# RP2040Breakout.net
KiCad netlist of a schematic drawn in EAGLE
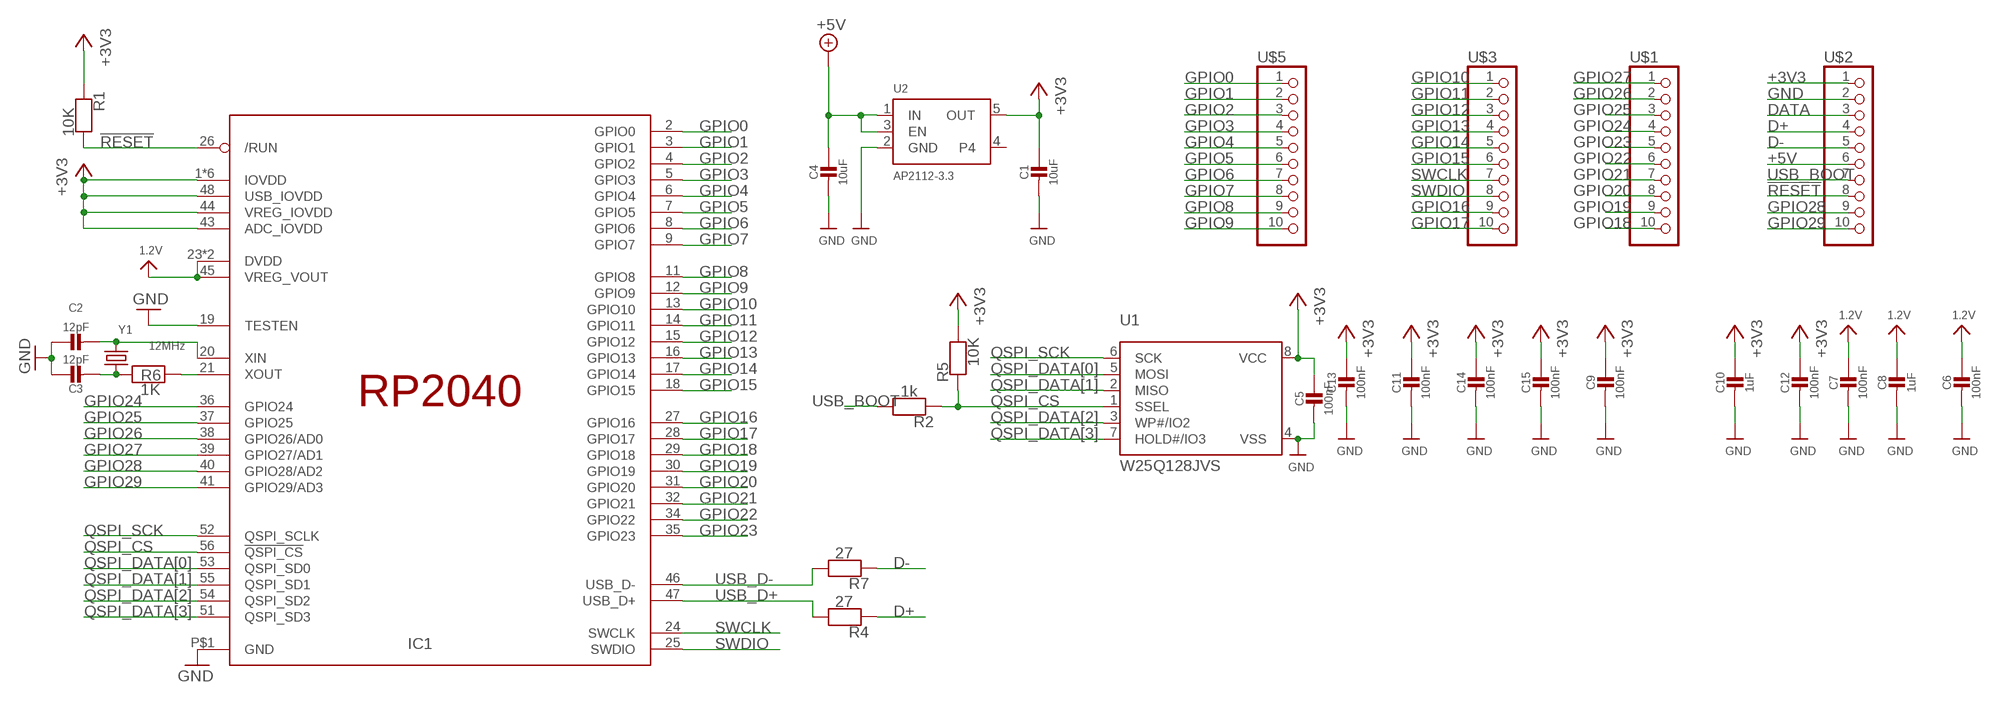
[diagram p0: schematic, sheet 1]

(export (version "E")
  (design (tool "Eeschema 10.0.6"))
  (components
    (comp (ref "C1")
      (value "10uF")
      (footprint "eagle-import:_0805MP")
      (libsource (lib "eagle-import") (part "CAP_CERAMIC_0805MP"))
    )
    (comp (ref "C2")
      (value "12pF")
      (footprint "eagle-import:_0402NO")
      (libsource (lib "eagle-import") (part "CAP_CERAMIC_0402NO"))
    )
    (comp (ref "C3")
      (value "12pF")
      (footprint "eagle-import:_0402NO")
      (libsource (lib "eagle-import") (part "CAP_CERAMIC_0402NO"))
    )
    (comp (ref "C4")
      (value "10uF")
      (footprint "eagle-import:_0805MP")
      (libsource (lib "eagle-import") (part "CAP_CERAMIC_0805MP"))
    )
    (comp (ref "C5")
      (value "100nF")
      (footprint "eagle-import:_0402NO")
      (libsource (lib "eagle-import") (part "CAP_CERAMIC_0402NO"))
    )
    (comp (ref "C6")
      (value "100nF")
      (footprint "eagle-import:_0402NO")
      (libsource (lib "eagle-import") (part "CAP_CERAMIC_0402NO"))
    )
    (comp (ref "C7")
      (value "100nF")
      (footprint "eagle-import:_0402NO")
      (libsource (lib "eagle-import") (part "CAP_CERAMIC_0402NO"))
    )
    (comp (ref "C8")
      (value "1uF")
      (footprint "eagle-import:_0402NO")
      (libsource (lib "eagle-import") (part "CAP_CERAMIC_0402NO"))
    )
    (comp (ref "C9")
      (value "100nF")
      (footprint "eagle-import:_0402NO")
      (libsource (lib "eagle-import") (part "CAP_CERAMIC_0402NO"))
    )
    (comp (ref "C10")
      (value "1uF")
      (footprint "eagle-import:_0402NO")
      (libsource (lib "eagle-import") (part "CAP_CERAMIC_0402NO"))
    )
    (comp (ref "C11")
      (value "100nF")
      (footprint "eagle-import:_0402NO")
      (libsource (lib "eagle-import") (part "CAP_CERAMIC_0402NO"))
    )
    (comp (ref "C12")
      (value "100nF")
      (footprint "eagle-import:_0402NO")
      (libsource (lib "eagle-import") (part "CAP_CERAMIC_0402NO"))
    )
    (comp (ref "C13")
      (value "100nF")
      (footprint "eagle-import:_0402NO")
      (libsource (lib "eagle-import") (part "CAP_CERAMIC_0402NO"))
    )
    (comp (ref "C14")
      (value "100nF")
      (footprint "eagle-import:_0402NO")
      (libsource (lib "eagle-import") (part "CAP_CERAMIC_0402NO"))
    )
    (comp (ref "C15")
      (value "100nF")
      (footprint "eagle-import:_0402NO")
      (libsource (lib "eagle-import") (part "CAP_CERAMIC_0402NO"))
    )
    (comp (ref "IC1")
      (value "RP2040_QFN56")
      (footprint "eagle-import:QFN56_7MM_REDUCEDEPAD")
      (libsource (lib "eagle-import") (part "RP2040_QFN56"))
    )
    (comp (ref "R1")
      (value "10K")
      (footprint "eagle-import:_0402NO")
      (libsource (lib "eagle-import") (part "RESISTOR_0402NO"))
    )
    (comp (ref "R2")
      (value "1k")
      (footprint "eagle-import:_0402NO")
      (libsource (lib "eagle-import") (part "RESISTOR_0402NO"))
    )
    (comp (ref "R4")
      (value "27")
      (footprint "eagle-import:_0402NO")
      (libsource (lib "eagle-import") (part "RESISTOR_0402NO"))
    )
    (comp (ref "R5")
      (value "10K")
      (footprint "eagle-import:_0402NO")
      (libsource (lib "eagle-import") (part "RESISTOR_0402NO"))
    )
    (comp (ref "R6")
      (value "1K")
      (footprint "eagle-import:_0402NO")
      (libsource (lib "eagle-import") (part "RESISTOR_0402NO"))
    )
    (comp (ref "R7")
      (value "27")
      (footprint "eagle-import:_0402NO")
      (libsource (lib "eagle-import") (part "RESISTOR_0402NO"))
    )
    (comp (ref "U$1")
      (value "HEADER-1X10ROUND")
      (footprint "eagle-import:1X10_ROUND")
      (libsource (lib "eagle-import") (part "HEADER-1X10ROUND"))
    )
    (comp (ref "U$2")
      (value "HEADER-1X10ROUND")
      (footprint "eagle-import:1X10_ROUND")
      (libsource (lib "eagle-import") (part "HEADER-1X10ROUND"))
    )
    (comp (ref "U$3")
      (value "HEADER-1X10ROUND")
      (footprint "eagle-import:1X10_ROUND")
      (libsource (lib "eagle-import") (part "HEADER-1X10ROUND"))
    )
    (comp (ref "U$5")
      (value "HEADER-1X10ROUND")
      (footprint "eagle-import:1X10_ROUND")
      (libsource (lib "eagle-import") (part "HEADER-1X10ROUND"))
    )
    (comp (ref "U1")
      (value "W25Q128JVS")
      (footprint "eagle-import:SOIC8_208MIL")
      (libsource (lib "eagle-import") (part "SPIFLASH_8PIN208MIL"))
    )
    (comp (ref "U2")
      (value "AP2112-3.3")
      (footprint "eagle-import:SOT23-5@1")
      (libsource (lib "eagle-import") (part "VREG_SOT23-5"))
    )
    (comp (ref "Y1")
      (value "12MHz")
      (footprint "eagle-import:CRYSTAL-SMD-5X3")
      (libsource (lib "eagle-import") (part "CRYSTALCRYSTAL-SMD-5X3-12MHZ"))
    )
  )
  (nets
    (net (code "1") (name "+3V3") (class "Default")
      (node (ref "C1") (pin "1") (pinfunction "1_1") (pintype "passive"))
      (node (ref "C10") (pin "1") (pinfunction "1_1") (pintype "passive"))
      (node (ref "C11") (pin "1") (pinfunction "1_1") (pintype "passive"))
      (node (ref "C12") (pin "1") (pinfunction "1_1") (pintype "passive"))
      (node (ref "C13") (pin "1") (pinfunction "1_1") (pintype "passive"))
      (node (ref "C14") (pin "1") (pinfunction "1_1") (pintype "passive"))
      (node (ref "C15") (pin "1") (pinfunction "1_1") (pintype "passive"))
      (node (ref "C5") (pin "1") (pinfunction "1_1") (pintype "passive"))
      (node (ref "C9") (pin "1") (pinfunction "1_1") (pintype "passive"))
      (node (ref "IC1") (pin "1") (pinfunction "IOVDD_1") (pintype "power_in"))
      (node (ref "IC1") (pin "10") (pinfunction "IOVDD_10") (pintype "power_in"))
      (node (ref "IC1") (pin "22") (pinfunction "IOVDD_22") (pintype "power_in"))
      (node (ref "IC1") (pin "33") (pinfunction "IOVDD_33") (pintype "power_in"))
      (node (ref "IC1") (pin "42") (pinfunction "IOVDD_42") (pintype "power_in"))
      (node (ref "IC1") (pin "43") (pinfunction "ADC_IOVDD_43") (pintype "power_in"))
      (node (ref "IC1") (pin "44") (pinfunction "VREG_IOVDD_44") (pintype "power_in"))
      (node (ref "IC1") (pin "48") (pinfunction "USB_IOVDD_48") (pintype "power_in"))
      (node (ref "IC1") (pin "49") (pinfunction "IOVDD_49") (pintype "power_in"))
      (node (ref "R1") (pin "1") (pinfunction "1_1") (pintype "passive"))
      (node (ref "R5") (pin "2") (pinfunction "2_2") (pintype "passive"))
      (node (ref "U$2") (pin "1") (pinfunction "1_1") (pintype "passive"))
      (node (ref "U1") (pin "8") (pinfunction "VCC_8") (pintype "bidirectional"))
      (node (ref "U2") (pin "5") (pinfunction "OUT_5") (pintype "power_in"))
    )
    (net (code "2") (name "+5V") (class "Default")
      (node (ref "C4") (pin "1") (pinfunction "1_1") (pintype "passive"))
      (node (ref "U$2") (pin "6") (pinfunction "6_6") (pintype "passive"))
      (node (ref "U2") (pin "1") (pinfunction "IN_1") (pintype "power_in"))
      (node (ref "U2") (pin "3") (pinfunction "EN_3") (pintype "input"))
    )
    (net (code "3") (name "/D+") (class "Default")
      (node (ref "R4") (pin "1") (pinfunction "1_1") (pintype "passive"))
      (node (ref "U$2") (pin "4") (pinfunction "4_4") (pintype "passive"))
    )
    (net (code "4") (name "/D-") (class "Default")
      (node (ref "R7") (pin "1") (pinfunction "1_1") (pintype "passive"))
      (node (ref "U$2") (pin "5") (pinfunction "5_5") (pintype "passive"))
    )
    (net (code "5") (name "/DATA") (class "Default")
      (node (ref "U$2") (pin "3") (pinfunction "3_3") (pintype "passive"))
    )
    (net (code "6") (name "/GPIO0") (class "Default")
      (node (ref "IC1") (pin "2") (pinfunction "GPIO0_2") (pintype "bidirectional"))
      (node (ref "U$5") (pin "1") (pinfunction "1_1") (pintype "passive"))
    )
    (net (code "7") (name "/GPIO1") (class "Default")
      (node (ref "IC1") (pin "3") (pinfunction "GPIO1_3") (pintype "bidirectional"))
      (node (ref "U$5") (pin "2") (pinfunction "2_2") (pintype "passive"))
    )
    (net (code "8") (name "/GPIO2") (class "Default")
      (node (ref "IC1") (pin "4") (pinfunction "GPIO2_4") (pintype "bidirectional"))
      (node (ref "U$5") (pin "3") (pinfunction "3_3") (pintype "passive"))
    )
    (net (code "9") (name "/GPIO3") (class "Default")
      (node (ref "IC1") (pin "5") (pinfunction "GPIO3_5") (pintype "bidirectional"))
      (node (ref "U$5") (pin "4") (pinfunction "4_4") (pintype "passive"))
    )
    (net (code "10") (name "/GPIO4") (class "Default")
      (node (ref "IC1") (pin "6") (pinfunction "GPIO4_6") (pintype "bidirectional"))
      (node (ref "U$5") (pin "5") (pinfunction "5_5") (pintype "passive"))
    )
    (net (code "11") (name "/GPIO5") (class "Default")
      (node (ref "IC1") (pin "7") (pinfunction "GPIO5_7") (pintype "bidirectional"))
      (node (ref "U$5") (pin "6") (pinfunction "6_6") (pintype "passive"))
    )
    (net (code "12") (name "/GPIO6") (class "Default")
      (node (ref "IC1") (pin "8") (pinfunction "GPIO6_8") (pintype "bidirectional"))
      (node (ref "U$5") (pin "7") (pinfunction "7_7") (pintype "passive"))
    )
    (net (code "13") (name "/GPIO7") (class "Default")
      (node (ref "IC1") (pin "9") (pinfunction "GPIO7_9") (pintype "bidirectional"))
      (node (ref "U$5") (pin "8") (pinfunction "8_8") (pintype "passive"))
    )
    (net (code "14") (name "/GPIO8") (class "Default")
      (node (ref "IC1") (pin "11") (pinfunction "GPIO8_11") (pintype "bidirectional"))
      (node (ref "U$5") (pin "9") (pinfunction "9_9") (pintype "passive"))
    )
    (net (code "15") (name "/GPIO9") (class "Default")
      (node (ref "IC1") (pin "12") (pinfunction "GPIO9_12") (pintype "bidirectional"))
      (node (ref "U$5") (pin "10") (pinfunction "10_10") (pintype "passive"))
    )
    (net (code "16") (name "/GPIO10") (class "Default")
      (node (ref "IC1") (pin "13") (pinfunction "GPIO10_13") (pintype "bidirectional"))
      (node (ref "U$3") (pin "1") (pinfunction "1_1") (pintype "passive"))
    )
    (net (code "17") (name "/GPIO11") (class "Default")
      (node (ref "IC1") (pin "14") (pinfunction "GPIO11_14") (pintype "bidirectional"))
      (node (ref "U$3") (pin "2") (pinfunction "2_2") (pintype "passive"))
    )
    (net (code "18") (name "/GPIO12") (class "Default")
      (node (ref "IC1") (pin "15") (pinfunction "GPIO12_15") (pintype "bidirectional"))
      (node (ref "U$3") (pin "3") (pinfunction "3_3") (pintype "passive"))
    )
    (net (code "19") (name "/GPIO13") (class "Default")
      (node (ref "IC1") (pin "16") (pinfunction "GPIO13_16") (pintype "bidirectional"))
      (node (ref "U$3") (pin "4") (pinfunction "4_4") (pintype "passive"))
    )
    (net (code "20") (name "/GPIO14") (class "Default")
      (node (ref "IC1") (pin "17") (pinfunction "GPIO14_17") (pintype "bidirectional"))
      (node (ref "U$3") (pin "5") (pinfunction "5_5") (pintype "passive"))
    )
    (net (code "21") (name "/GPIO15") (class "Default")
      (node (ref "IC1") (pin "18") (pinfunction "GPIO15_18") (pintype "bidirectional"))
      (node (ref "U$3") (pin "6") (pinfunction "6_6") (pintype "passive"))
    )
    (net (code "22") (name "/GPIO16") (class "Default")
      (node (ref "IC1") (pin "27") (pinfunction "GPIO16_27") (pintype "bidirectional"))
      (node (ref "U$3") (pin "9") (pinfunction "9_9") (pintype "passive"))
    )
    (net (code "23") (name "/GPIO17") (class "Default")
      (node (ref "IC1") (pin "28") (pinfunction "GPIO17_28") (pintype "bidirectional"))
      (node (ref "U$3") (pin "10") (pinfunction "10_10") (pintype "passive"))
    )
    (net (code "24") (name "/GPIO18") (class "Default")
      (node (ref "IC1") (pin "29") (pinfunction "GPIO18_29") (pintype "bidirectional"))
      (node (ref "U$1") (pin "10") (pinfunction "10_10") (pintype "passive"))
    )
    (net (code "25") (name "/GPIO19") (class "Default")
      (node (ref "IC1") (pin "30") (pinfunction "GPIO19_30") (pintype "bidirectional"))
      (node (ref "U$1") (pin "9") (pinfunction "9_9") (pintype "passive"))
    )
    (net (code "26") (name "/GPIO20") (class "Default")
      (node (ref "IC1") (pin "31") (pinfunction "GPIO20_31") (pintype "bidirectional"))
      (node (ref "U$1") (pin "8") (pinfunction "8_8") (pintype "passive"))
    )
    (net (code "27") (name "/GPIO21") (class "Default")
      (node (ref "IC1") (pin "32") (pinfunction "GPIO21_32") (pintype "bidirectional"))
      (node (ref "U$1") (pin "7") (pinfunction "7_7") (pintype "passive"))
    )
    (net (code "28") (name "/GPIO22") (class "Default")
      (node (ref "IC1") (pin "34") (pinfunction "GPIO22_34") (pintype "bidirectional"))
      (node (ref "U$1") (pin "6") (pinfunction "6_6") (pintype "passive"))
    )
    (net (code "29") (name "/GPIO23") (class "Default")
      (node (ref "IC1") (pin "35") (pinfunction "GPIO23_35") (pintype "bidirectional"))
      (node (ref "U$1") (pin "5") (pinfunction "5_5") (pintype "passive"))
    )
    (net (code "30") (name "/GPIO24") (class "Default")
      (node (ref "IC1") (pin "36") (pinfunction "GPIO24_36") (pintype "bidirectional"))
      (node (ref "U$1") (pin "4") (pinfunction "4_4") (pintype "passive"))
    )
    (net (code "31") (name "/GPIO25") (class "Default")
      (node (ref "IC1") (pin "37") (pinfunction "GPIO25_37") (pintype "bidirectional"))
      (node (ref "U$1") (pin "3") (pinfunction "3_3") (pintype "passive"))
    )
    (net (code "32") (name "/GPIO26") (class "Default")
      (node (ref "IC1") (pin "38") (pinfunction "GPIO26/AD0_38") (pintype "bidirectional"))
      (node (ref "U$1") (pin "2") (pinfunction "2_2") (pintype "passive"))
    )
    (net (code "33") (name "/GPIO27") (class "Default")
      (node (ref "IC1") (pin "39") (pinfunction "GPIO27/AD1_39") (pintype "bidirectional"))
      (node (ref "U$1") (pin "1") (pinfunction "1_1") (pintype "passive"))
    )
    (net (code "34") (name "/GPIO28") (class "Default")
      (node (ref "IC1") (pin "40") (pinfunction "GPIO28/AD2_40") (pintype "bidirectional"))
      (node (ref "U$2") (pin "9") (pinfunction "9_9") (pintype "passive"))
    )
    (net (code "35") (name "/GPIO29") (class "Default")
      (node (ref "IC1") (pin "41") (pinfunction "GPIO29/AD3_41") (pintype "bidirectional"))
      (node (ref "U$2") (pin "10") (pinfunction "10_10") (pintype "passive"))
    )
    (net (code "36") (name "/QSPI_CS") (class "Default")
      (node (ref "IC1") (pin "56") (pinfunction "~{QSPI_CS}_56") (pintype "bidirectional"))
      (node (ref "R2") (pin "1") (pinfunction "1_1") (pintype "passive"))
      (node (ref "R5") (pin "1") (pinfunction "1_1") (pintype "passive"))
      (node (ref "U1") (pin "1") (pinfunction "SSEL_1") (pintype "bidirectional"))
    )
    (net (code "37") (name "/QSPI_DATA[0]") (class "Default")
      (node (ref "IC1") (pin "53") (pinfunction "QSPI_SD0_53") (pintype "bidirectional"))
      (node (ref "U1") (pin "5") (pinfunction "MOSI_5") (pintype "bidirectional"))
    )
    (net (code "38") (name "/QSPI_DATA[1]") (class "Default")
      (node (ref "IC1") (pin "55") (pinfunction "QSPI_SD1_55") (pintype "bidirectional"))
      (node (ref "U1") (pin "2") (pinfunction "MISO_2") (pintype "bidirectional"))
    )
    (net (code "39") (name "/QSPI_DATA[2]") (class "Default")
      (node (ref "IC1") (pin "54") (pinfunction "QSPI_SD2_54") (pintype "bidirectional"))
      (node (ref "U1") (pin "3") (pinfunction "WP#/IO2_3") (pintype "bidirectional"))
    )
    (net (code "40") (name "/QSPI_DATA[3]") (class "Default")
      (node (ref "IC1") (pin "51") (pinfunction "QSPI_SD3_51") (pintype "bidirectional"))
      (node (ref "U1") (pin "7") (pinfunction "HOLD#/IO3_7") (pintype "bidirectional"))
    )
    (net (code "41") (name "/QSPI_SCK") (class "Default")
      (node (ref "IC1") (pin "52") (pinfunction "QSPI_SCLK_52") (pintype "bidirectional"))
      (node (ref "U1") (pin "6") (pinfunction "SCK_6") (pintype "bidirectional"))
    )
    (net (code "42") (name "/SWCLK") (class "Default")
      (node (ref "IC1") (pin "24") (pinfunction "SWCLK_24") (pintype "bidirectional"))
      (node (ref "U$3") (pin "7") (pinfunction "7_7") (pintype "passive"))
    )
    (net (code "43") (name "/SWDIO") (class "Default")
      (node (ref "IC1") (pin "25") (pinfunction "SWDIO_25") (pintype "bidirectional"))
      (node (ref "U$3") (pin "8") (pinfunction "8_8") (pintype "passive"))
    )
    (net (code "44") (name "/USB_BOOT") (class "Default")
      (node (ref "R2") (pin "2") (pinfunction "2_2") (pintype "passive"))
      (node (ref "U$2") (pin "7") (pinfunction "7_7") (pintype "passive"))
    )
    (net (code "45") (name "/USB_D+") (class "Default")
      (node (ref "IC1") (pin "47") (pinfunction "USB_D+_47") (pintype "bidirectional"))
      (node (ref "R4") (pin "2") (pinfunction "2_2") (pintype "passive"))
    )
    (net (code "46") (name "/USB_D-") (class "Default")
      (node (ref "IC1") (pin "46") (pinfunction "USB_D-_46") (pintype "bidirectional"))
      (node (ref "R7") (pin "2") (pinfunction "2_2") (pintype "passive"))
    )
    (net (code "47") (name "/~{RESET}") (class "Default")
      (node (ref "IC1") (pin "26") (pinfunction "/RUN_26") (pintype "bidirectional"))
      (node (ref "R1") (pin "2") (pinfunction "2_2") (pintype "passive"))
      (node (ref "U$2") (pin "8") (pinfunction "8_8") (pintype "passive"))
    )
    (net (code "48") (name "1.2V") (class "Default")
      (node (ref "C6") (pin "1") (pinfunction "1_1") (pintype "passive"))
      (node (ref "C7") (pin "1") (pinfunction "1_1") (pintype "passive"))
      (node (ref "C8") (pin "1") (pinfunction "1_1") (pintype "passive"))
      (node (ref "IC1") (pin "23") (pinfunction "DVDD_23") (pintype "power_in"))
      (node (ref "IC1") (pin "45") (pinfunction "VREG_VOUT_45") (pintype "power_in"))
      (node (ref "IC1") (pin "50") (pinfunction "DVDD_50") (pintype "power_in"))
    )
    (net (code "49") (name "GND") (class "Default")
      (node (ref "C1") (pin "2") (pinfunction "2_2") (pintype "passive"))
      (node (ref "C10") (pin "2") (pinfunction "2_2") (pintype "passive"))
      (node (ref "C11") (pin "2") (pinfunction "2_2") (pintype "passive"))
      (node (ref "C12") (pin "2") (pinfunction "2_2") (pintype "passive"))
      (node (ref "C13") (pin "2") (pinfunction "2_2") (pintype "passive"))
      (node (ref "C14") (pin "2") (pinfunction "2_2") (pintype "passive"))
      (node (ref "C15") (pin "2") (pinfunction "2_2") (pintype "passive"))
      (node (ref "C2") (pin "1") (pinfunction "1_1") (pintype "passive"))
      (node (ref "C3") (pin "1") (pinfunction "1_1") (pintype "passive"))
      (node (ref "C4") (pin "2") (pinfunction "2_2") (pintype "passive"))
      (node (ref "C5") (pin "2") (pinfunction "2_2") (pintype "passive"))
      (node (ref "C6") (pin "2") (pinfunction "2_2") (pintype "passive"))
      (node (ref "C7") (pin "2") (pinfunction "2_2") (pintype "passive"))
      (node (ref "C8") (pin "2") (pinfunction "2_2") (pintype "passive"))
      (node (ref "C9") (pin "2") (pinfunction "2_2") (pintype "passive"))
      (node (ref "IC1") (pin "19") (pinfunction "TESTEN_19") (pintype "input"))
      (node (ref "IC1") (pin "P$1") (pinfunction "GND_P$1") (pintype "power_in"))
      (node (ref "U$2") (pin "2") (pinfunction "2_2") (pintype "passive"))
      (node (ref "U1") (pin "4") (pinfunction "VSS_4") (pintype "bidirectional"))
      (node (ref "U2") (pin "2") (pinfunction "GND_2") (pintype "power_in"))
    )
    (net (code "50") (name "Net-(C3-Pad2)") (class "Default")
      (node (ref "C3") (pin "2") (pinfunction "2_2") (pintype "passive"))
      (node (ref "R6") (pin "1") (pinfunction "1_1") (pintype "passive"))
      (node (ref "Y1") (pin "1") (pinfunction "1_1") (pintype "passive"))
    )
    (net (code "51") (name "Net-(IC1-XIN)") (class "Default")
      (node (ref "C2") (pin "2") (pinfunction "2_2") (pintype "passive"))
      (node (ref "IC1") (pin "20") (pinfunction "XIN_20") (pintype "input"))
      (node (ref "Y1") (pin "3") (pinfunction "2_3") (pintype "passive"))
    )
    (net (code "52") (name "Net-(IC1-XOUT)") (class "Default")
      (node (ref "IC1") (pin "21") (pinfunction "XOUT_21") (pintype "output"))
      (node (ref "R6") (pin "2") (pinfunction "2_2") (pintype "passive"))
    )
    (net (code "53") (name "unconnected-(U2-P4-Pad4)") (class "Default")
      (node (ref "U2") (pin "4") (pinfunction "P4_4") (pintype "bidirectional"))
    )
  )
)
